# E17-15-TSAL_LED.net
KiCad netlist of a schematic drawn in Altium Designer
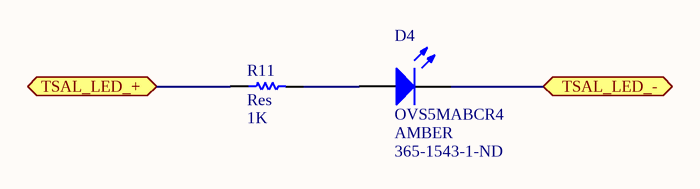
[diagram p0: E17-15-TSAL_LED.SchDoc]

(export (version "E")
  (design (tool "Eeschema 10.0.6"))
  (components
    (comp (ref "D4")
      (value "OVS5MABCR4")
      (footprint "OVS5MABCR4")
      (description "Typical AMBER LED")
      (fields
        (field (name "COLOUR") "AMBER")
        (field (name "SUPPLIER PART NUMBER 1") "365-1543-1-ND")
        (field (name "PUBLISHER") "Altium Limited")
      )
      (libsource (lib "LEDs") (part "OVS5MABCR4"))
    )
    (comp (ref "R11")
      (value "Res")
      (footprint "3216[1206]")
      (description "Surface Mount Resistor")
      (fields (field (name "ALTIUM_VALUE") "1K") (field (name "PUBLISHER") "Altium Limited"))
      (libsource (lib "Resistors") (part "Res"))
    )
  )
  (nets
    (net (code "1") (name "/TSAL_LED_+") (class "Default")
      (node (ref "R11") (pin "1") (pinfunction "1_1") (pintype "passive"))
    )
    (net (code "2") (name "/TSAL_LED_-") (class "Default")
      (node (ref "D4") (pin "2") (pinfunction "K_2") (pintype "passive"))
    )
    (net (code "3") (name "Net-(D4-A)") (class "Default")
      (node (ref "D4") (pin "1") (pinfunction "A_1") (pintype "passive"))
      (node (ref "R11") (pin "2") (pinfunction "2_2") (pintype "passive"))
    )
  )
)
